# Water_Counter_Nathan_Amir.net
KiCad netlist of a schematic drawn in EasyEDA
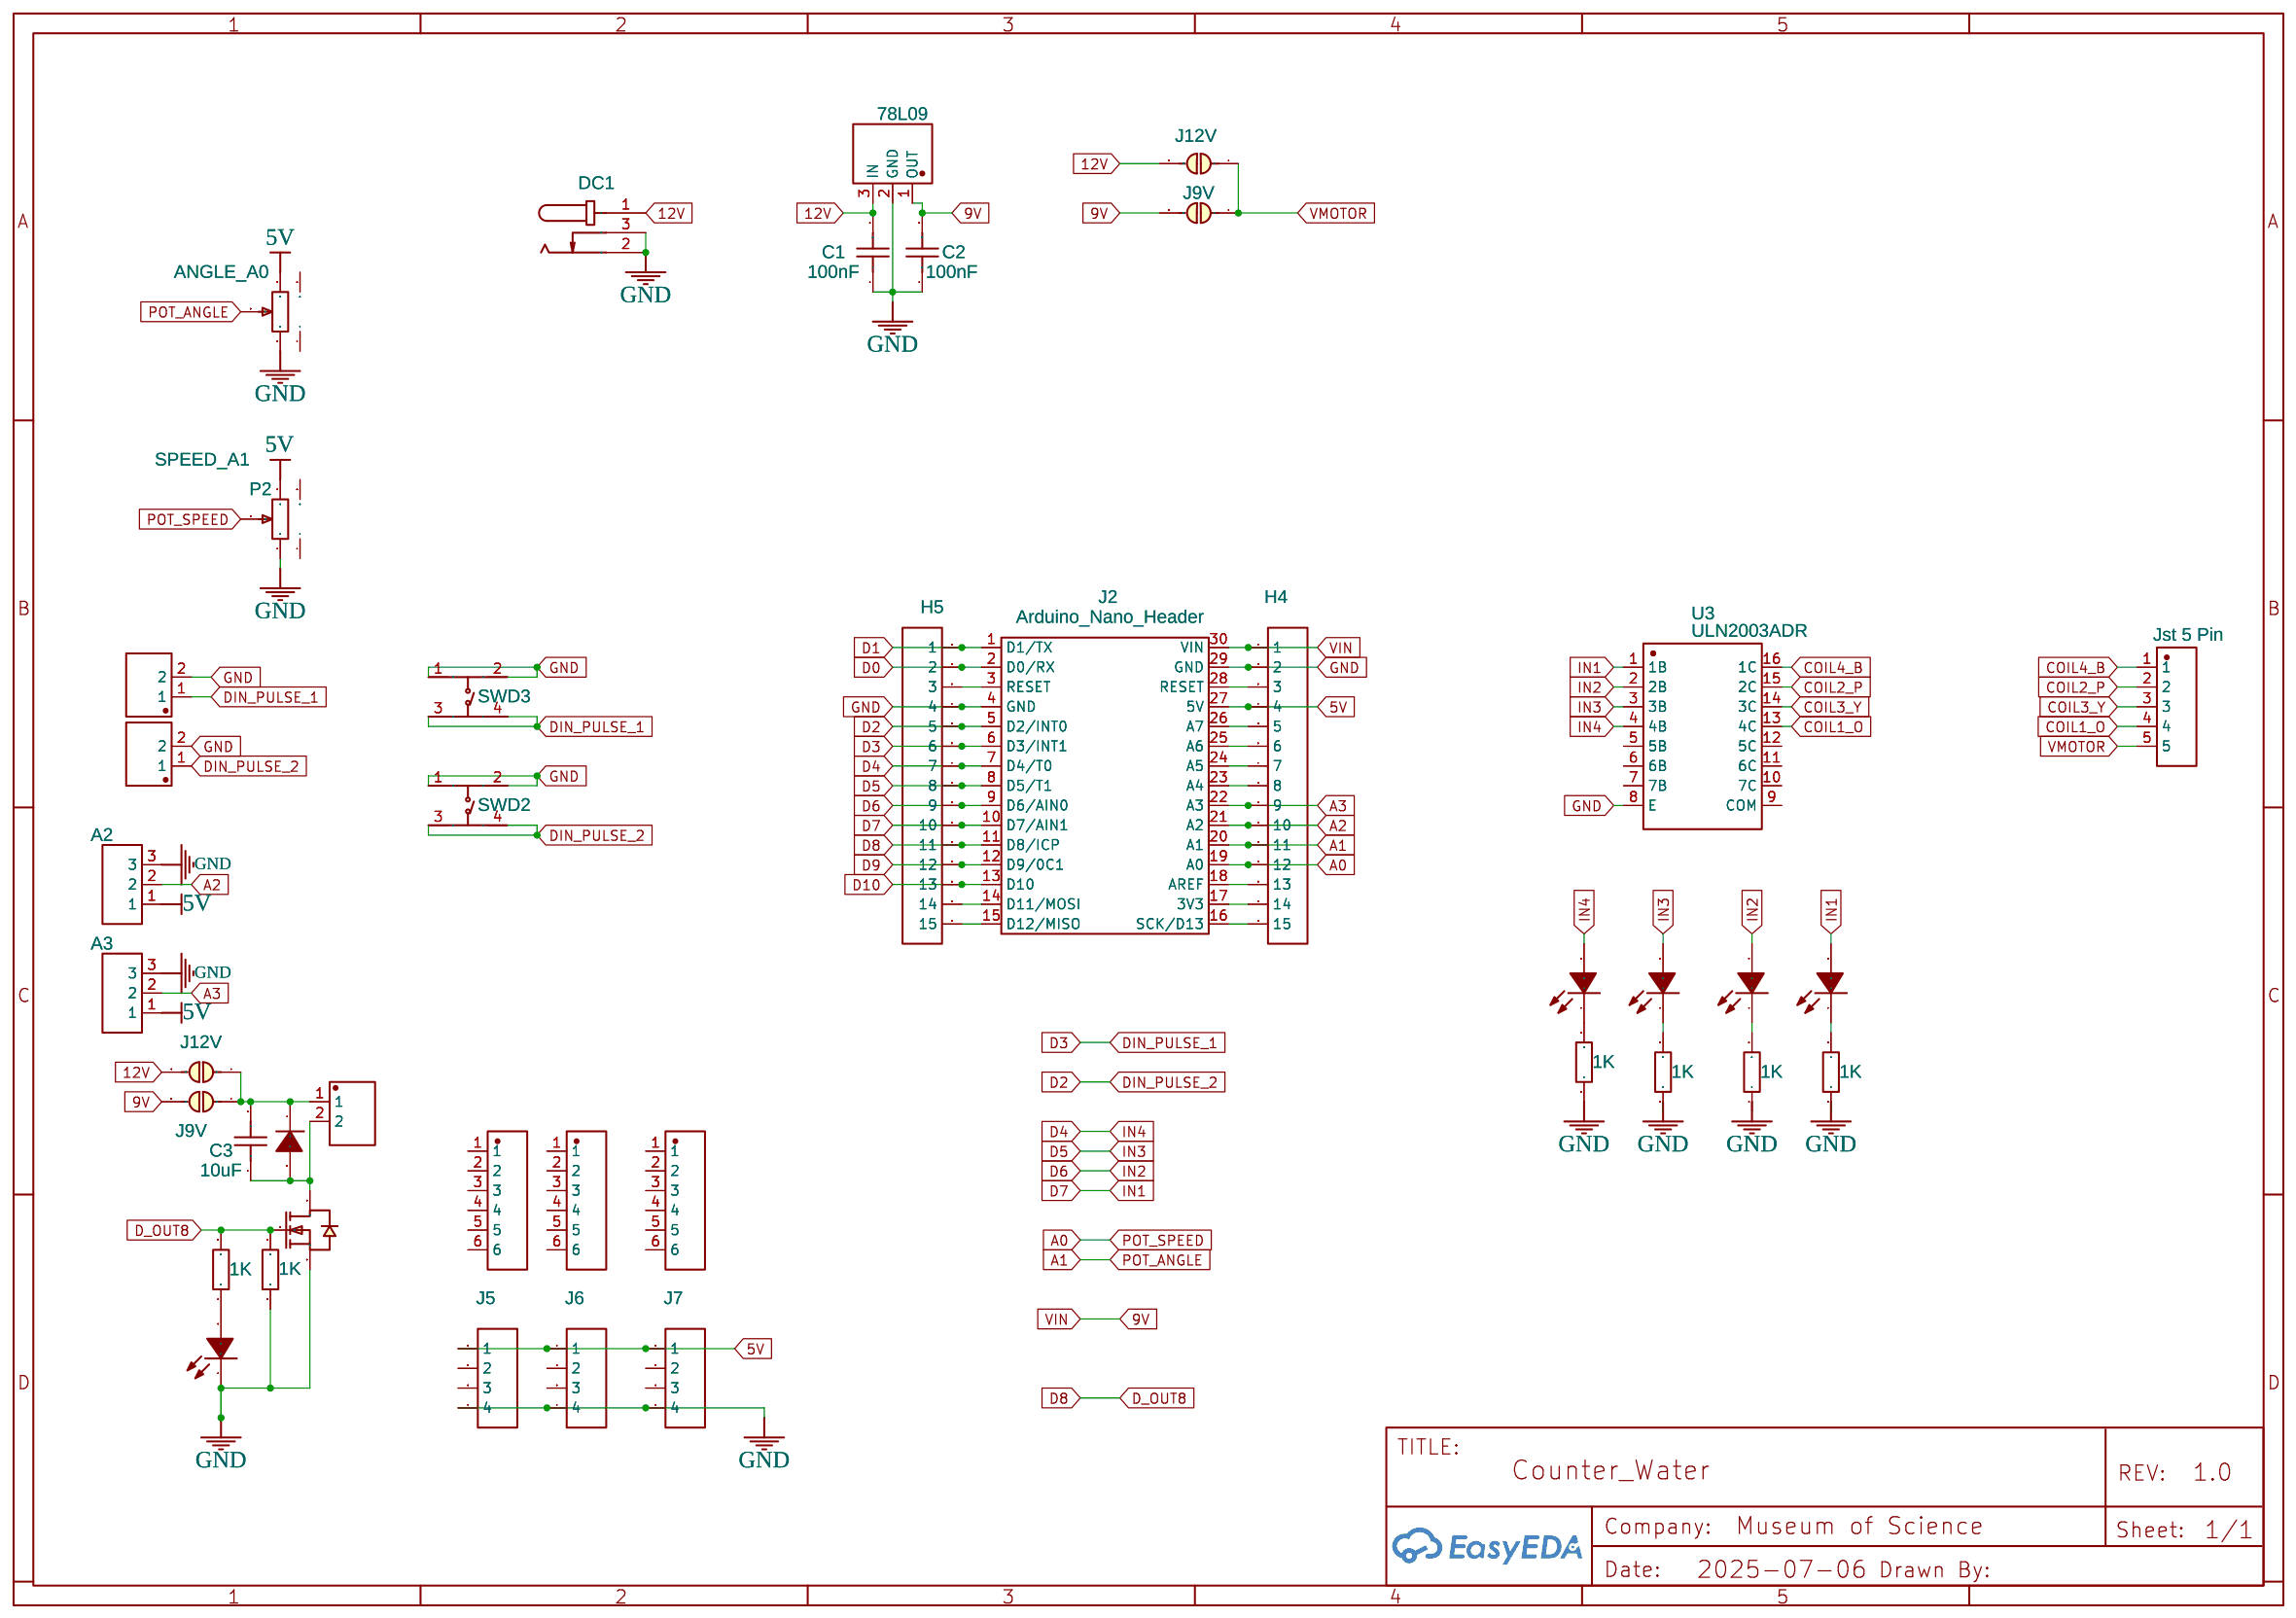
[diagram p0: schematic sheet]

(export (version "E")
  (design (tool "Eeschema 10.0.6"))
  (components
    (comp (ref "A2") (value "FK2510") (libsource (lib "") (part "kf2510_3A")))
    (comp (ref "A3") (value "FK2510") (libsource (lib "") (part "kf2510_3A")))
    (comp (ref "C1")
      (value "100nF")
      (fields
        (field (name "Manufacturer Part") "CC0603KRX7R9BB104")
        (field (name "Manufacturer") "YAGEO(国巨)")
      )
      (libsource (lib "") (part "CC0603KRX7R9BB104"))
    )
    (comp (ref "C2")
      (value "100nF")
      (fields
        (field (name "Manufacturer Part") "CC0603KRX7R9BB104")
        (field (name "Manufacturer") "YAGEO(国巨)")
      )
      (libsource (lib "") (part "CC0603KRX7R9BB104"))
    )
    (comp (ref "C3")
      (value "10uF")
      (fields
        (field (name "Manufacturer Part") "GRM21BR61H106KE43L")
        (field (name "Manufacturer") "muRata(村田)")
      )
      (libsource (lib "") (part "GRM21BR61H106KE43L"))
    )
    (comp (ref "D2")
      (value "KF2510-2A")
      (fields (field (name "Manufacturer") "BOOMELE"))
      (libsource (lib "") (part "KF2510-2A_1"))
    )
    (comp (ref "D3")
      (value "KF2510-2A")
      (fields (field (name "Manufacturer") "BOOMELE"))
      (libsource (lib "") (part "KF2510-2A_1"))
    )
    (comp (ref "DC1")
      (value "DC")
      (fields (field (name "Manufacturer Part") "DC005-2.0MM") (field (name "Manufacturer") "SOFNG"))
      (libsource (lib "") (part "DC005-2.0MM"))
    )
    (comp (ref "ECON1")
      (value "D_OUT8")
      (fields (field (name "Manufacturer Part") "KF2510-2A") (field (name "Manufacturer") "BOOMELE"))
      (libsource (lib "") (part "KF2510-2A"))
    )
    (comp (ref "EDM1")
      (value "1N4007")
      (fields (field (name "Manufacturer Part") "1N4007F") (field (name "Manufacturer") "SK"))
      (libsource (lib "") (part "1N4007F"))
    )
    (comp (ref "EQ1")
      (value "Q")
      (fields (field (name "Manufacturer Part") "AO3400") (field (name "Manufacturer") "ElecSuper(静芯微）"))
      (libsource (lib "") (part "JSM2302"))
    )
    (comp (ref "ERG1")
      (value "1K")
      (fields (field (name "Manufacturer Part") "0603WAF1001T5E") (field (name "Manufacturer") "UniOhm"))
      (libsource (lib "") (part "0603WAF1001T5E_1"))
    )
    (comp (ref "ERL1")
      (value "1K")
      (fields (field (name "Manufacturer Part") "0603WAF1001T5E") (field (name "Manufacturer") "UniOhm"))
      (libsource (lib "") (part "0603WAF1001T5E"))
    )
    (comp (ref "ERL2")
      (value "1K")
      (fields (field (name "Manufacturer Part") "0603WAF1001T5E") (field (name "Manufacturer") "UniOhm"))
      (libsource (lib "") (part "0603WAF1001T5E"))
    )
    (comp (ref "ERL3")
      (value "1K")
      (fields (field (name "Manufacturer Part") "0603WAF1001T5E") (field (name "Manufacturer") "UniOhm"))
      (libsource (lib "") (part "0603WAF1001T5E"))
    )
    (comp (ref "ERL4")
      (value "1K")
      (fields (field (name "Manufacturer Part") "0603WAF1001T5E") (field (name "Manufacturer") "UniOhm"))
      (libsource (lib "") (part "0603WAF1001T5E"))
    )
    (comp (ref "ERL5")
      (value "1K")
      (fields (field (name "Manufacturer Part") "0603WAF1001T5E") (field (name "Manufacturer") "UniOhm"))
      (libsource (lib "") (part "0603WAF1001T5E"))
    )
    (comp (ref "H4") (value "HDR-F-2.54_1x15") (libsource (lib "") (part "HDR-F-2.54_1x15")))
    (comp (ref "H5") (value "HDR-F-2.54_1x15") (libsource (lib "") (part "HDR-F-2.54_1x15_1")))
    (comp (ref "J2") (value "Arduino_Nano_Header") (libsource (lib "") (part "Arduino_Nano_Header")))
    (comp (ref "J5") (value "HDR-M-2.54_1x4") (libsource (lib "") (part "HDR-M-2.54_1x4")))
    (comp (ref "J5V_2") (value "J9V") (libsource (lib "") (part "JUMPER-SMT_2_2")))
    (comp (ref "J6") (value "HDR-M-2.54_1x4") (libsource (lib "") (part "HDR-M-2.54_1x4")))
    (comp (ref "J7") (value "HDR-M-2.54_1x4") (libsource (lib "") (part "HDR-M-2.54_1x4")))
    (comp (ref "J9V_1") (value "J9V") (libsource (lib "") (part "JUMPER-SMT_2")))
    (comp (ref "J12V_1") (value "J12V") (libsource (lib "") (part "JUMPER-SMT_2_1")))
    (comp (ref "J12V_2") (value "J12V") (libsource (lib "") (part "JUMPER-SMT_2_1")))
    (comp (ref "LED1")
      (value "KT-0603R")
      (fields (field (name "Manufacturer") "KENTO"))
      (libsource (lib "") (part "KT-0603R"))
    )
    (comp (ref "LED2")
      (value "KT-0603R")
      (fields (field (name "Manufacturer") "KENTO"))
      (libsource (lib "") (part "KT-0603R"))
    )
    (comp (ref "LED3")
      (value "KT-0603R")
      (fields (field (name "Manufacturer") "KENTO"))
      (libsource (lib "") (part "KT-0603R"))
    )
    (comp (ref "LED4")
      (value "KT-0603R")
      (fields (field (name "Manufacturer") "KENTO"))
      (libsource (lib "") (part "KT-0603R"))
    )
    (comp (ref "LED5")
      (value "KT-0603R")
      (fields (field (name "Manufacturer") "KENTO"))
      (libsource (lib "") (part "KT-0603R"))
    )
    (comp (ref "P2")
      (value "SPEED_A1")
      (fields (field (name "Manufacturer Part") "长柄旋转电位器"))
      (libsource (lib "") (part "长柄旋转电位器"))
    )
    (comp (ref "P3")
      (value "ANGLE_A0")
      (fields (field (name "Manufacturer Part") "长柄旋转电位器"))
      (libsource (lib "") (part "长柄旋转电位器"))
    )
    (comp (ref "SWD2")
      (value "TC-6610-7-160G")
      (fields (field (name "Manufacturer") "HCTL(华灿天禄)"))
      (libsource (lib "") (part "TC-6610-7-160G"))
    )
    (comp (ref "SWD3")
      (value "TC-6610-7-160G")
      (fields (field (name "Manufacturer") "HCTL(华灿天禄)"))
      (libsource (lib "") (part "TC-6610-7-160G"))
    )
    (comp (ref "U1")
      (value "78L09")
      (fields (field (name "Manufacturer") "CBI(创基)"))
      (libsource (lib "") (part "78L09U 78L09"))
    )
    (comp (ref "U2")
      (value "Jst 5 Pin")
      (fields (field (name "Manufacturer") "Vicky"))
      (libsource (lib "") (part "Jst 5 Pin"))
    )
    (comp (ref "U3")
      (value "ULN2003ADR")
      (fields (field (name "Manufacturer") "TI(德州仪器)"))
      (libsource (lib "") (part "ULN2003ADR"))
    )
    (comp (ref "U4")
      (value "HC-PM254-5.0H-1X6PZ")
      (fields
        (field (name "Manufacturer Part") "HC-PM254-5.0H-1x6PZ")
        (field (name "Manufacturer") "HC(虹成电子)")
      )
      (libsource (lib "") (part "HC-PM254-5.0H-1X6PZ"))
    )
    (comp (ref "U5")
      (value "HC-PM254-5.0H-1X6PZ")
      (fields
        (field (name "Manufacturer Part") "HC-PM254-5.0H-1x6PZ")
        (field (name "Manufacturer") "HC(虹成电子)")
      )
      (libsource (lib "") (part "HC-PM254-5.0H-1X6PZ"))
    )
    (comp (ref "U6")
      (value "HC-PM254-5.0H-1X6PZ")
      (fields
        (field (name "Manufacturer Part") "HC-PM254-5.0H-1x6PZ")
        (field (name "Manufacturer") "HC(虹成电子)")
      )
      (libsource (lib "") (part "HC-PM254-5.0H-1X6PZ"))
    )
  )
  (nets
    (net (code "1") (name "5V") (class "Default")
      (node (ref "A2") (pin "1") (pinfunction "1_1") (pintype "unspecified"))
      (node (ref "A3") (pin "1") (pinfunction "1_1") (pintype "unspecified"))
      (node (ref "H4") (pin "4") (pinfunction "4_4") (pintype "unspecified"))
      (node (ref "J2") (pin "27") (pinfunction "5V_27") (pintype "unspecified"))
      (node (ref "J5") (pin "1") (pinfunction "1_1") (pintype "unspecified"))
      (node (ref "J6") (pin "1") (pinfunction "1_1") (pintype "unspecified"))
      (node (ref "J7") (pin "1") (pinfunction "1_1") (pintype "unspecified"))
      (node (ref "P2") (pin "3") (pinfunction "3_3") (pintype "input"))
      (node (ref "P3") (pin "3") (pinfunction "3_3") (pintype "input"))
    )
    (net (code "2") (name "9V") (class "Default")
      (node (ref "C2") (pin "2") (pinfunction "2_2") (pintype "unspecified"))
      (node (ref "H4") (pin "1") (pinfunction "1_1") (pintype "unspecified"))
      (node (ref "J2") (pin "30") (pinfunction "VIN_30") (pintype "unspecified"))
      (node (ref "J5V_2") (pin "2") (pinfunction "2_2") (pintype "bidirectional"))
      (node (ref "J9V_1") (pin "2") (pinfunction "2_2") (pintype "bidirectional"))
      (node (ref "U1") (pin "1") (pinfunction "OUT_1") (pintype "unspecified"))
    )
    (net (code "3") (name "12V") (class "Default")
      (node (ref "C1") (pin "2") (pinfunction "2_2") (pintype "unspecified"))
      (node (ref "DC1") (pin "1") (pinfunction "1_1") (pintype "unspecified"))
      (node (ref "J12V_1") (pin "2") (pinfunction "2_2") (pintype "bidirectional"))
      (node (ref "J12V_2") (pin "2") (pinfunction "2_2") (pintype "bidirectional"))
      (node (ref "U1") (pin "3") (pinfunction "IN_3") (pintype "unspecified"))
    )
    (net (code "4") (name "A0") (class "Default")
      (node (ref "H4") (pin "12") (pinfunction "12_12") (pintype "unspecified"))
      (node (ref "J2") (pin "19") (pinfunction "A0_19") (pintype "unspecified"))
      (node (ref "P2") (pin "2") (pinfunction "2_2") (pintype "input"))
    )
    (net (code "5") (name "A1") (class "Default")
      (node (ref "H4") (pin "11") (pinfunction "11_11") (pintype "unspecified"))
      (node (ref "J2") (pin "20") (pinfunction "A1_20") (pintype "unspecified"))
      (node (ref "P3") (pin "2") (pinfunction "2_2") (pintype "input"))
    )
    (net (code "6") (name "A2") (class "Default")
      (node (ref "A2") (pin "2") (pinfunction "2_2") (pintype "unspecified"))
      (node (ref "H4") (pin "10") (pinfunction "10_10") (pintype "unspecified"))
      (node (ref "J2") (pin "21") (pinfunction "A2_21") (pintype "unspecified"))
    )
    (net (code "7") (name "A3") (class "Default")
      (node (ref "A3") (pin "2") (pinfunction "2_2") (pintype "unspecified"))
      (node (ref "H4") (pin "9") (pinfunction "9_9") (pintype "unspecified"))
      (node (ref "J2") (pin "22") (pinfunction "A3_22") (pintype "unspecified"))
    )
    (net (code "8") (name "COIL1_O") (class "Default")
      (node (ref "U2") (pin "4") (pinfunction "4_4") (pintype "unspecified"))
      (node (ref "U3") (pin "13") (pinfunction "4C_13") (pintype "unspecified"))
    )
    (net (code "9") (name "COIL2_P") (class "Default")
      (node (ref "U2") (pin "2") (pinfunction "2_2") (pintype "unspecified"))
      (node (ref "U3") (pin "15") (pinfunction "2C_15") (pintype "unspecified"))
    )
    (net (code "10") (name "COIL3_Y") (class "Default")
      (node (ref "U2") (pin "3") (pinfunction "3_3") (pintype "unspecified"))
      (node (ref "U3") (pin "14") (pinfunction "3C_14") (pintype "unspecified"))
    )
    (net (code "11") (name "COIL4_B") (class "Default")
      (node (ref "U2") (pin "1") (pinfunction "1_1") (pintype "unspecified"))
      (node (ref "U3") (pin "16") (pinfunction "1C_16") (pintype "unspecified"))
    )
    (net (code "12") (name "D0") (class "Default")
      (node (ref "H5") (pin "2") (pinfunction "2_2") (pintype "unspecified"))
      (node (ref "J2") (pin "2") (pinfunction "D0/RX_2") (pintype "unspecified"))
    )
    (net (code "13") (name "D1") (class "Default")
      (node (ref "H5") (pin "1") (pinfunction "1_1") (pintype "unspecified"))
      (node (ref "J2") (pin "1") (pinfunction "D1/TX_1") (pintype "unspecified"))
    )
    (net (code "14") (name "D2") (class "Default")
      (node (ref "D2") (pin "1") (pinfunction "1_1") (pintype "unspecified"))
      (node (ref "H5") (pin "5") (pinfunction "5_5") (pintype "unspecified"))
      (node (ref "J2") (pin "5") (pinfunction "D2/INT0_5") (pintype "unspecified"))
      (node (ref "SWD2") (pin "3") (pinfunction "3_3") (pintype "unspecified"))
      (node (ref "SWD2") (pin "4") (pinfunction "4_4") (pintype "unspecified"))
    )
    (net (code "15") (name "D3") (class "Default")
      (node (ref "D3") (pin "1") (pinfunction "1_1") (pintype "unspecified"))
      (node (ref "H5") (pin "6") (pinfunction "6_6") (pintype "unspecified"))
      (node (ref "J2") (pin "6") (pinfunction "D3/INT1_6") (pintype "unspecified"))
      (node (ref "SWD3") (pin "3") (pinfunction "3_3") (pintype "unspecified"))
      (node (ref "SWD3") (pin "4") (pinfunction "4_4") (pintype "unspecified"))
    )
    (net (code "16") (name "D4") (class "Default")
      (node (ref "H5") (pin "7") (pinfunction "7_7") (pintype "unspecified"))
      (node (ref "J2") (pin "7") (pinfunction "D4/T0_7") (pintype "unspecified"))
      (node (ref "LED5") (pin "2") (pinfunction "A_2") (pintype "unspecified"))
      (node (ref "U3") (pin "4") (pinfunction "4B_4") (pintype "unspecified"))
    )
    (net (code "17") (name "D5") (class "Default")
      (node (ref "H5") (pin "8") (pinfunction "8_8") (pintype "unspecified"))
      (node (ref "J2") (pin "8") (pinfunction "D5/T1_8") (pintype "unspecified"))
      (node (ref "LED4") (pin "2") (pinfunction "A_2") (pintype "unspecified"))
      (node (ref "U3") (pin "3") (pinfunction "3B_3") (pintype "unspecified"))
    )
    (net (code "18") (name "D6") (class "Default")
      (node (ref "H5") (pin "9") (pinfunction "9_9") (pintype "unspecified"))
      (node (ref "J2") (pin "9") (pinfunction "D6/AIN0_9") (pintype "unspecified"))
      (node (ref "LED3") (pin "2") (pinfunction "A_2") (pintype "unspecified"))
      (node (ref "U3") (pin "2") (pinfunction "2B_2") (pintype "unspecified"))
    )
    (net (code "19") (name "D7") (class "Default")
      (node (ref "H5") (pin "10") (pinfunction "10_10") (pintype "unspecified"))
      (node (ref "J2") (pin "10") (pinfunction "D7/AIN1_10") (pintype "unspecified"))
      (node (ref "LED2") (pin "2") (pinfunction "A_2") (pintype "unspecified"))
      (node (ref "U3") (pin "1") (pinfunction "1B_1") (pintype "unspecified"))
    )
    (net (code "20") (name "D8") (class "Default")
      (node (ref "EQ1") (pin "1") (pinfunction "G_1") (pintype "unspecified"))
      (node (ref "ERG1") (pin "2") (pinfunction "2_2") (pintype "input"))
      (node (ref "ERL5") (pin "2") (pinfunction "2_2") (pintype "input"))
      (node (ref "H5") (pin "11") (pinfunction "11_11") (pintype "unspecified"))
      (node (ref "J2") (pin "11") (pinfunction "D8/ICP_11") (pintype "unspecified"))
    )
    (net (code "21") (name "D9") (class "Default")
      (node (ref "H5") (pin "12") (pinfunction "12_12") (pintype "unspecified"))
      (node (ref "J2") (pin "12") (pinfunction "D9/0C1_12") (pintype "unspecified"))
    )
    (net (code "22") (name "D10") (class "Default")
      (node (ref "H5") (pin "13") (pinfunction "13_13") (pintype "unspecified"))
      (node (ref "J2") (pin "13") (pinfunction "D10_13") (pintype "unspecified"))
    )
    (net (code "23") (name "GND") (class "Default")
      (node (ref "A2") (pin "3") (pinfunction "3_3") (pintype "unspecified"))
      (node (ref "A3") (pin "3") (pinfunction "3_3") (pintype "unspecified"))
      (node (ref "C1") (pin "1") (pinfunction "1_1") (pintype "unspecified"))
      (node (ref "C2") (pin "1") (pinfunction "1_1") (pintype "unspecified"))
      (node (ref "D2") (pin "2") (pinfunction "2_2") (pintype "unspecified"))
      (node (ref "D3") (pin "2") (pinfunction "2_2") (pintype "unspecified"))
      (node (ref "DC1") (pin "2") (pinfunction "2_2") (pintype "unspecified"))
      (node (ref "DC1") (pin "3") (pinfunction "3_3") (pintype "unspecified"))
      (node (ref "EQ1") (pin "2") (pinfunction "S_2") (pintype "unspecified"))
      (node (ref "ERG1") (pin "1") (pinfunction "1_1") (pintype "input"))
      (node (ref "ERL1") (pin "1") (pinfunction "1_1") (pintype "input"))
      (node (ref "ERL2") (pin "1") (pinfunction "1_1") (pintype "input"))
      (node (ref "ERL3") (pin "1") (pinfunction "1_1") (pintype "input"))
      (node (ref "ERL4") (pin "1") (pinfunction "1_1") (pintype "input"))
      (node (ref "H4") (pin "2") (pinfunction "2_2") (pintype "unspecified"))
      (node (ref "H5") (pin "4") (pinfunction "4_4") (pintype "unspecified"))
      (node (ref "J2") (pin "29") (pinfunction "GND_29") (pintype "unspecified"))
      (node (ref "J2") (pin "4") (pinfunction "GND_4") (pintype "unspecified"))
      (node (ref "J5") (pin "4") (pinfunction "4_4") (pintype "unspecified"))
      (node (ref "J6") (pin "4") (pinfunction "4_4") (pintype "unspecified"))
      (node (ref "J7") (pin "4") (pinfunction "4_4") (pintype "unspecified"))
      (node (ref "LED1") (pin "1") (pinfunction "K_1") (pintype "unspecified"))
      (node (ref "P2") (pin "1") (pinfunction "1_1") (pintype "input"))
      (node (ref "P3") (pin "1") (pinfunction "1_1") (pintype "input"))
      (node (ref "SWD2") (pin "1") (pinfunction "1_1") (pintype "unspecified"))
      (node (ref "SWD2") (pin "2") (pinfunction "2_2") (pintype "unspecified"))
      (node (ref "SWD3") (pin "1") (pinfunction "1_1") (pintype "unspecified"))
      (node (ref "SWD3") (pin "2") (pinfunction "2_2") (pintype "unspecified"))
      (node (ref "U1") (pin "2") (pinfunction "GND_2") (pintype "unspecified"))
      (node (ref "U3") (pin "8") (pinfunction "E_8") (pintype "unspecified"))
    )
    (net (code "24") (name "Net-(EDM1-A)") (class "Default")
      (node (ref "C3") (pin "1") (pinfunction "1_1") (pintype "unspecified"))
      (node (ref "ECON1") (pin "2") (pinfunction "2_2") (pintype "unspecified"))
      (node (ref "EDM1") (pin "2") (pinfunction "A_2") (pintype "unspecified"))
      (node (ref "EQ1") (pin "3") (pinfunction "D_3") (pintype "unspecified"))
    )
    (net (code "25") (name "Net-(EDM1-C)") (class "Default")
      (node (ref "C3") (pin "2") (pinfunction "2_2") (pintype "unspecified"))
      (node (ref "ECON1") (pin "1") (pinfunction "1_1") (pintype "unspecified"))
      (node (ref "EDM1") (pin "1") (pinfunction "C_1") (pintype "unspecified"))
      (node (ref "J12V_2") (pin "1") (pinfunction "1_1") (pintype "bidirectional"))
      (node (ref "J5V_2") (pin "1") (pinfunction "1_1") (pintype "bidirectional"))
    )
    (net (code "26") (name "Net-(H4-Pad3)") (class "Default")
      (node (ref "H4") (pin "3") (pinfunction "3_3") (pintype "unspecified"))
      (node (ref "J2") (pin "28") (pinfunction "RESET_28") (pintype "unspecified"))
    )
    (net (code "27") (name "Net-(H5-Pad3)") (class "Default")
      (node (ref "H5") (pin "3") (pinfunction "3_3") (pintype "unspecified"))
      (node (ref "J2") (pin "3") (pinfunction "RESET_3") (pintype "unspecified"))
    )
    (net (code "28") (name "Net-(J2-3V3)") (class "Default")
      (node (ref "H4") (pin "14") (pinfunction "14_14") (pintype "unspecified"))
      (node (ref "J2") (pin "17") (pinfunction "3V3_17") (pintype "unspecified"))
    )
    (net (code "29") (name "Net-(J2-A4)") (class "Default")
      (node (ref "H4") (pin "8") (pinfunction "8_8") (pintype "unspecified"))
      (node (ref "J2") (pin "23") (pinfunction "A4_23") (pintype "unspecified"))
    )
    (net (code "30") (name "Net-(J2-A5)") (class "Default")
      (node (ref "H4") (pin "7") (pinfunction "7_7") (pintype "unspecified"))
      (node (ref "J2") (pin "24") (pinfunction "A5_24") (pintype "unspecified"))
    )
    (net (code "31") (name "Net-(J2-A6)") (class "Default")
      (node (ref "H4") (pin "6") (pinfunction "6_6") (pintype "unspecified"))
      (node (ref "J2") (pin "25") (pinfunction "A6_25") (pintype "unspecified"))
    )
    (net (code "32") (name "Net-(J2-A7)") (class "Default")
      (node (ref "H4") (pin "5") (pinfunction "5_5") (pintype "unspecified"))
      (node (ref "J2") (pin "26") (pinfunction "A7_26") (pintype "unspecified"))
    )
    (net (code "33") (name "Net-(J2-AREF)") (class "Default")
      (node (ref "H4") (pin "13") (pinfunction "13_13") (pintype "unspecified"))
      (node (ref "J2") (pin "18") (pinfunction "AREF_18") (pintype "unspecified"))
    )
    (net (code "34") (name "Net-(J2-D11{slash}MOSI)") (class "Default")
      (node (ref "H5") (pin "14") (pinfunction "14_14") (pintype "unspecified"))
      (node (ref "J2") (pin "14") (pinfunction "D11/MOSI_14") (pintype "unspecified"))
    )
    (net (code "35") (name "Net-(J2-D12{slash}MISO)") (class "Default")
      (node (ref "H5") (pin "15") (pinfunction "15_15") (pintype "unspecified"))
      (node (ref "J2") (pin "15") (pinfunction "D12/MISO_15") (pintype "unspecified"))
    )
    (net (code "36") (name "Net-(J2-SCK{slash}D13)") (class "Default")
      (node (ref "H4") (pin "15") (pinfunction "15_15") (pintype "unspecified"))
      (node (ref "J2") (pin "16") (pinfunction "SCK/D13_16") (pintype "unspecified"))
    )
    (net (code "37") (name "Net-(LED1-A)") (class "Default")
      (node (ref "ERL5") (pin "1") (pinfunction "1_1") (pintype "input"))
      (node (ref "LED1") (pin "2") (pinfunction "A_2") (pintype "unspecified"))
    )
    (net (code "38") (name "Net-(LED2-K)") (class "Default")
      (node (ref "ERL3") (pin "2") (pinfunction "2_2") (pintype "input"))
      (node (ref "LED2") (pin "1") (pinfunction "K_1") (pintype "unspecified"))
    )
    (net (code "39") (name "Net-(LED3-K)") (class "Default")
      (node (ref "ERL2") (pin "2") (pinfunction "2_2") (pintype "input"))
      (node (ref "LED3") (pin "1") (pinfunction "K_1") (pintype "unspecified"))
    )
    (net (code "40") (name "Net-(LED4-K)") (class "Default")
      (node (ref "ERL4") (pin "2") (pinfunction "2_2") (pintype "input"))
      (node (ref "LED4") (pin "1") (pinfunction "K_1") (pintype "unspecified"))
    )
    (net (code "41") (name "Net-(LED5-K)") (class "Default")
      (node (ref "ERL1") (pin "2") (pinfunction "2_2") (pintype "input"))
      (node (ref "LED5") (pin "1") (pinfunction "K_1") (pintype "unspecified"))
    )
    (net (code "42") (name "VMOTOR") (class "Default")
      (node (ref "J12V_1") (pin "1") (pinfunction "1_1") (pintype "bidirectional"))
      (node (ref "J9V_1") (pin "1") (pinfunction "1_1") (pintype "bidirectional"))
      (node (ref "U2") (pin "5") (pinfunction "5_5") (pintype "unspecified"))
    )
    (net (code "43") (name "unconnected-(J5-Pad2)") (class "Default")
      (node (ref "J5") (pin "2") (pinfunction "2_2") (pintype "unspecified"))
    )
    (net (code "44") (name "unconnected-(J5-Pad3)") (class "Default")
      (node (ref "J5") (pin "3") (pinfunction "3_3") (pintype "unspecified"))
    )
    (net (code "45") (name "unconnected-(J6-Pad2)") (class "Default")
      (node (ref "J6") (pin "2") (pinfunction "2_2") (pintype "unspecified"))
    )
    (net (code "46") (name "unconnected-(J6-Pad3)") (class "Default")
      (node (ref "J6") (pin "3") (pinfunction "3_3") (pintype "unspecified"))
    )
    (net (code "47") (name "unconnected-(J7-Pad2)") (class "Default")
      (node (ref "J7") (pin "2") (pinfunction "2_2") (pintype "unspecified"))
    )
    (net (code "48") (name "unconnected-(J7-Pad3)") (class "Default")
      (node (ref "J7") (pin "3") (pinfunction "3_3") (pintype "unspecified"))
    )
    (net (code "49") (name "unconnected-(P2-Pad4)") (class "Default")
      (node (ref "P2") (pin "4") (pinfunction "4_4") (pintype "input"))
    )
    (net (code "50") (name "unconnected-(P2-Pad5)") (class "Default")
      (node (ref "P2") (pin "5") (pinfunction "5_5") (pintype "input"))
    )
    (net (code "51") (name "unconnected-(P3-Pad4)") (class "Default")
      (node (ref "P3") (pin "4") (pinfunction "4_4") (pintype "input"))
    )
    (net (code "52") (name "unconnected-(P3-Pad5)") (class "Default")
      (node (ref "P3") (pin "5") (pinfunction "5_5") (pintype "input"))
    )
    (net (code "53") (name "unconnected-(U3-5B-Pad5)") (class "Default")
      (node (ref "U3") (pin "5") (pinfunction "5B_5") (pintype "unspecified"))
    )
    (net (code "54") (name "unconnected-(U3-5C-Pad12)") (class "Default")
      (node (ref "U3") (pin "12") (pinfunction "5C_12") (pintype "unspecified"))
    )
    (net (code "55") (name "unconnected-(U3-6B-Pad6)") (class "Default")
      (node (ref "U3") (pin "6") (pinfunction "6B_6") (pintype "unspecified"))
    )
    (net (code "56") (name "unconnected-(U3-6C-Pad11)") (class "Default")
      (node (ref "U3") (pin "11") (pinfunction "6C_11") (pintype "unspecified"))
    )
    (net (code "57") (name "unconnected-(U3-7B-Pad7)") (class "Default")
      (node (ref "U3") (pin "7") (pinfunction "7B_7") (pintype "unspecified"))
    )
    (net (code "58") (name "unconnected-(U3-7C-Pad10)") (class "Default")
      (node (ref "U3") (pin "10") (pinfunction "7C_10") (pintype "unspecified"))
    )
    (net (code "59") (name "unconnected-(U3-COM-Pad9)") (class "Default")
      (node (ref "U3") (pin "9") (pinfunction "COM_9") (pintype "unspecified"))
    )
    (net (code "60") (name "unconnected-(U4-Pad1)") (class "Default")
      (node (ref "U4") (pin "1") (pinfunction "1_1") (pintype "unspecified"))
    )
    (net (code "61") (name "unconnected-(U4-Pad2)") (class "Default")
      (node (ref "U4") (pin "2") (pinfunction "2_2") (pintype "unspecified"))
    )
    (net (code "62") (name "unconnected-(U4-Pad3)") (class "Default")
      (node (ref "U4") (pin "3") (pinfunction "3_3") (pintype "unspecified"))
    )
    (net (code "63") (name "unconnected-(U4-Pad4)") (class "Default")
      (node (ref "U4") (pin "4") (pinfunction "4_4") (pintype "unspecified"))
    )
    (net (code "64") (name "unconnected-(U4-Pad5)") (class "Default")
      (node (ref "U4") (pin "5") (pinfunction "5_5") (pintype "unspecified"))
    )
    (net (code "65") (name "unconnected-(U4-Pad6)") (class "Default")
      (node (ref "U4") (pin "6") (pinfunction "6_6") (pintype "unspecified"))
    )
    (net (code "66") (name "unconnected-(U5-Pad1)") (class "Default")
      (node (ref "U5") (pin "1") (pinfunction "1_1") (pintype "unspecified"))
    )
    (net (code "67") (name "unconnected-(U5-Pad2)") (class "Default")
      (node (ref "U5") (pin "2") (pinfunction "2_2") (pintype "unspecified"))
    )
    (net (code "68") (name "unconnected-(U5-Pad3)") (class "Default")
      (node (ref "U5") (pin "3") (pinfunction "3_3") (pintype "unspecified"))
    )
    (net (code "69") (name "unconnected-(U5-Pad4)") (class "Default")
      (node (ref "U5") (pin "4") (pinfunction "4_4") (pintype "unspecified"))
    )
    (net (code "70") (name "unconnected-(U5-Pad5)") (class "Default")
      (node (ref "U5") (pin "5") (pinfunction "5_5") (pintype "unspecified"))
    )
    (net (code "71") (name "unconnected-(U5-Pad6)") (class "Default")
      (node (ref "U5") (pin "6") (pinfunction "6_6") (pintype "unspecified"))
    )
    (net (code "72") (name "unconnected-(U6-Pad1)") (class "Default")
      (node (ref "U6") (pin "1") (pinfunction "1_1") (pintype "unspecified"))
    )
    (net (code "73") (name "unconnected-(U6-Pad2)") (class "Default")
      (node (ref "U6") (pin "2") (pinfunction "2_2") (pintype "unspecified"))
    )
    (net (code "74") (name "unconnected-(U6-Pad3)") (class "Default")
      (node (ref "U6") (pin "3") (pinfunction "3_3") (pintype "unspecified"))
    )
    (net (code "75") (name "unconnected-(U6-Pad4)") (class "Default")
      (node (ref "U6") (pin "4") (pinfunction "4_4") (pintype "unspecified"))
    )
    (net (code "76") (name "unconnected-(U6-Pad5)") (class "Default")
      (node (ref "U6") (pin "5") (pinfunction "5_5") (pintype "unspecified"))
    )
    (net (code "77") (name "unconnected-(U6-Pad6)") (class "Default")
      (node (ref "U6") (pin "6") (pinfunction "6_6") (pintype "unspecified"))
    )
  )
)
